# LDO_C.net
KiCad netlist of a schematic drawn in Altium Designer
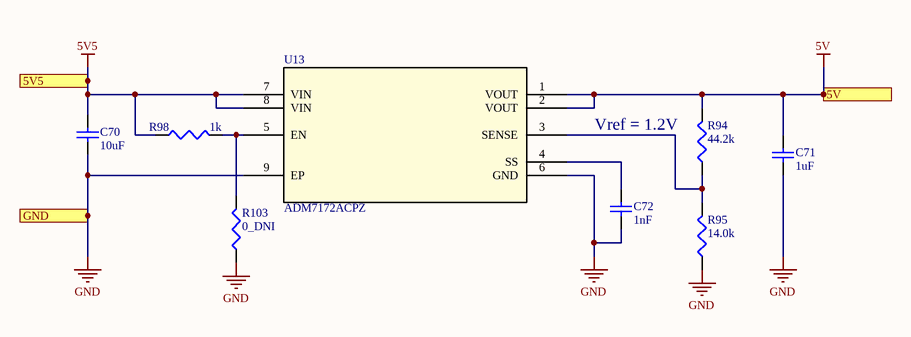
[diagram p0: LDO_C.SchDoc]

(export (version "E")
  (design (tool "Eeschema 10.0.6"))
  (components
    (comp (ref "C70")
      (value "10uF")
      (footprint "SMD-0603")
      (description "Ceramic Capacitor 0603")
      (libsource (lib "LCR") (part "CAP0603"))
    )
    (comp (ref "C71")
      (value "1uF")
      (footprint "SMD-0603")
      (description "Ceramic Capacitor 0603")
      (libsource (lib "LCR") (part "CAP0603"))
    )
    (comp (ref "C72")
      (value "1nF")
      (footprint "SMD-0603")
      (description "Ceramic Capacitor 0603")
      (libsource (lib "LCR") (part "CAP0603"))
    )
    (comp (ref "R94")
      (value "44.2k")
      (footprint "SMD-0603")
      (description "Resistor-0603")
      (libsource (lib "LCR") (part "RES0603"))
    )
    (comp (ref "R95")
      (value "14.0k")
      (footprint "SMD-0603")
      (description "Resistor-0603")
      (libsource (lib "LCR") (part "RES0603"))
    )
    (comp (ref "R98")
      (value "1k")
      (footprint "SMD-0603")
      (description "Resistor-0603")
      (libsource (lib "LCR") (part "RES0603"))
    )
    (comp (ref "R103")
      (value "0_DNI")
      (footprint "SMD-0603")
      (description "Resistor-0603")
      (libsource (lib "LCR") (part "RES0603"))
    )
    (comp (ref "U13")
      (value "ADM7172ACPZ")
      (footprint "LFCSP_WD-8")
      (description "6.5V, 2A, Ultralow Noise, High PSRR, Fast Transient Response CMOS LDO")
      (libsource (lib "PowerManagement") (part "ADM7172ACPZ"))
    )
  )
  (nets
    (net (code "1") (name "5V") (class "Default")
      (node (ref "C71") (pin "2") (pinfunction "2_2") (pintype "passive"))
      (node (ref "R94") (pin "2") (pinfunction "2_2") (pintype "passive"))
      (node (ref "U13") (pin "1") (pinfunction "VOUT_1") (pintype "passive"))
      (node (ref "U13") (pin "2") (pinfunction "VOUT_2") (pintype "passive"))
    )
    (net (code "2") (name "5V5") (class "Default")
      (node (ref "C70") (pin "2") (pinfunction "2_2") (pintype "passive"))
      (node (ref "R98") (pin "1") (pinfunction "1_1") (pintype "passive"))
      (node (ref "U13") (pin "7") (pinfunction "VIN_7") (pintype "passive"))
      (node (ref "U13") (pin "8") (pinfunction "VIN_8") (pintype "passive"))
    )
    (net (code "3") (name "GND") (class "Default")
      (node (ref "C70") (pin "1") (pinfunction "1_1") (pintype "passive"))
      (node (ref "C71") (pin "1") (pinfunction "1_1") (pintype "passive"))
      (node (ref "C72") (pin "2") (pinfunction "2_2") (pintype "passive"))
      (node (ref "R103") (pin "1") (pinfunction "1_1") (pintype "passive"))
      (node (ref "R95") (pin "1") (pinfunction "1_1") (pintype "passive"))
      (node (ref "U13") (pin "6") (pinfunction "GND_6") (pintype "passive"))
      (node (ref "U13") (pin "9") (pinfunction "EP_9") (pintype "passive"))
    )
    (net (code "4") (name "Net-(U13-EN)") (class "Default")
      (node (ref "R103") (pin "2") (pinfunction "2_2") (pintype "passive"))
      (node (ref "R98") (pin "2") (pinfunction "2_2") (pintype "passive"))
      (node (ref "U13") (pin "5") (pinfunction "EN_5") (pintype "passive"))
    )
    (net (code "5") (name "Net-(U13-SENSE)") (class "Default")
      (node (ref "R94") (pin "1") (pinfunction "1_1") (pintype "passive"))
      (node (ref "R95") (pin "2") (pinfunction "2_2") (pintype "passive"))
      (node (ref "U13") (pin "3") (pinfunction "SENSE_3") (pintype "passive"))
    )
    (net (code "6") (name "Net-(U13-SS)") (class "Default")
      (node (ref "C72") (pin "1") (pinfunction "1_1") (pintype "passive"))
      (node (ref "U13") (pin "4") (pinfunction "SS_4") (pintype "passive"))
    )
  )
)
